# Johnny_5.net
KiCad netlist of a schematic drawn in EAGLE
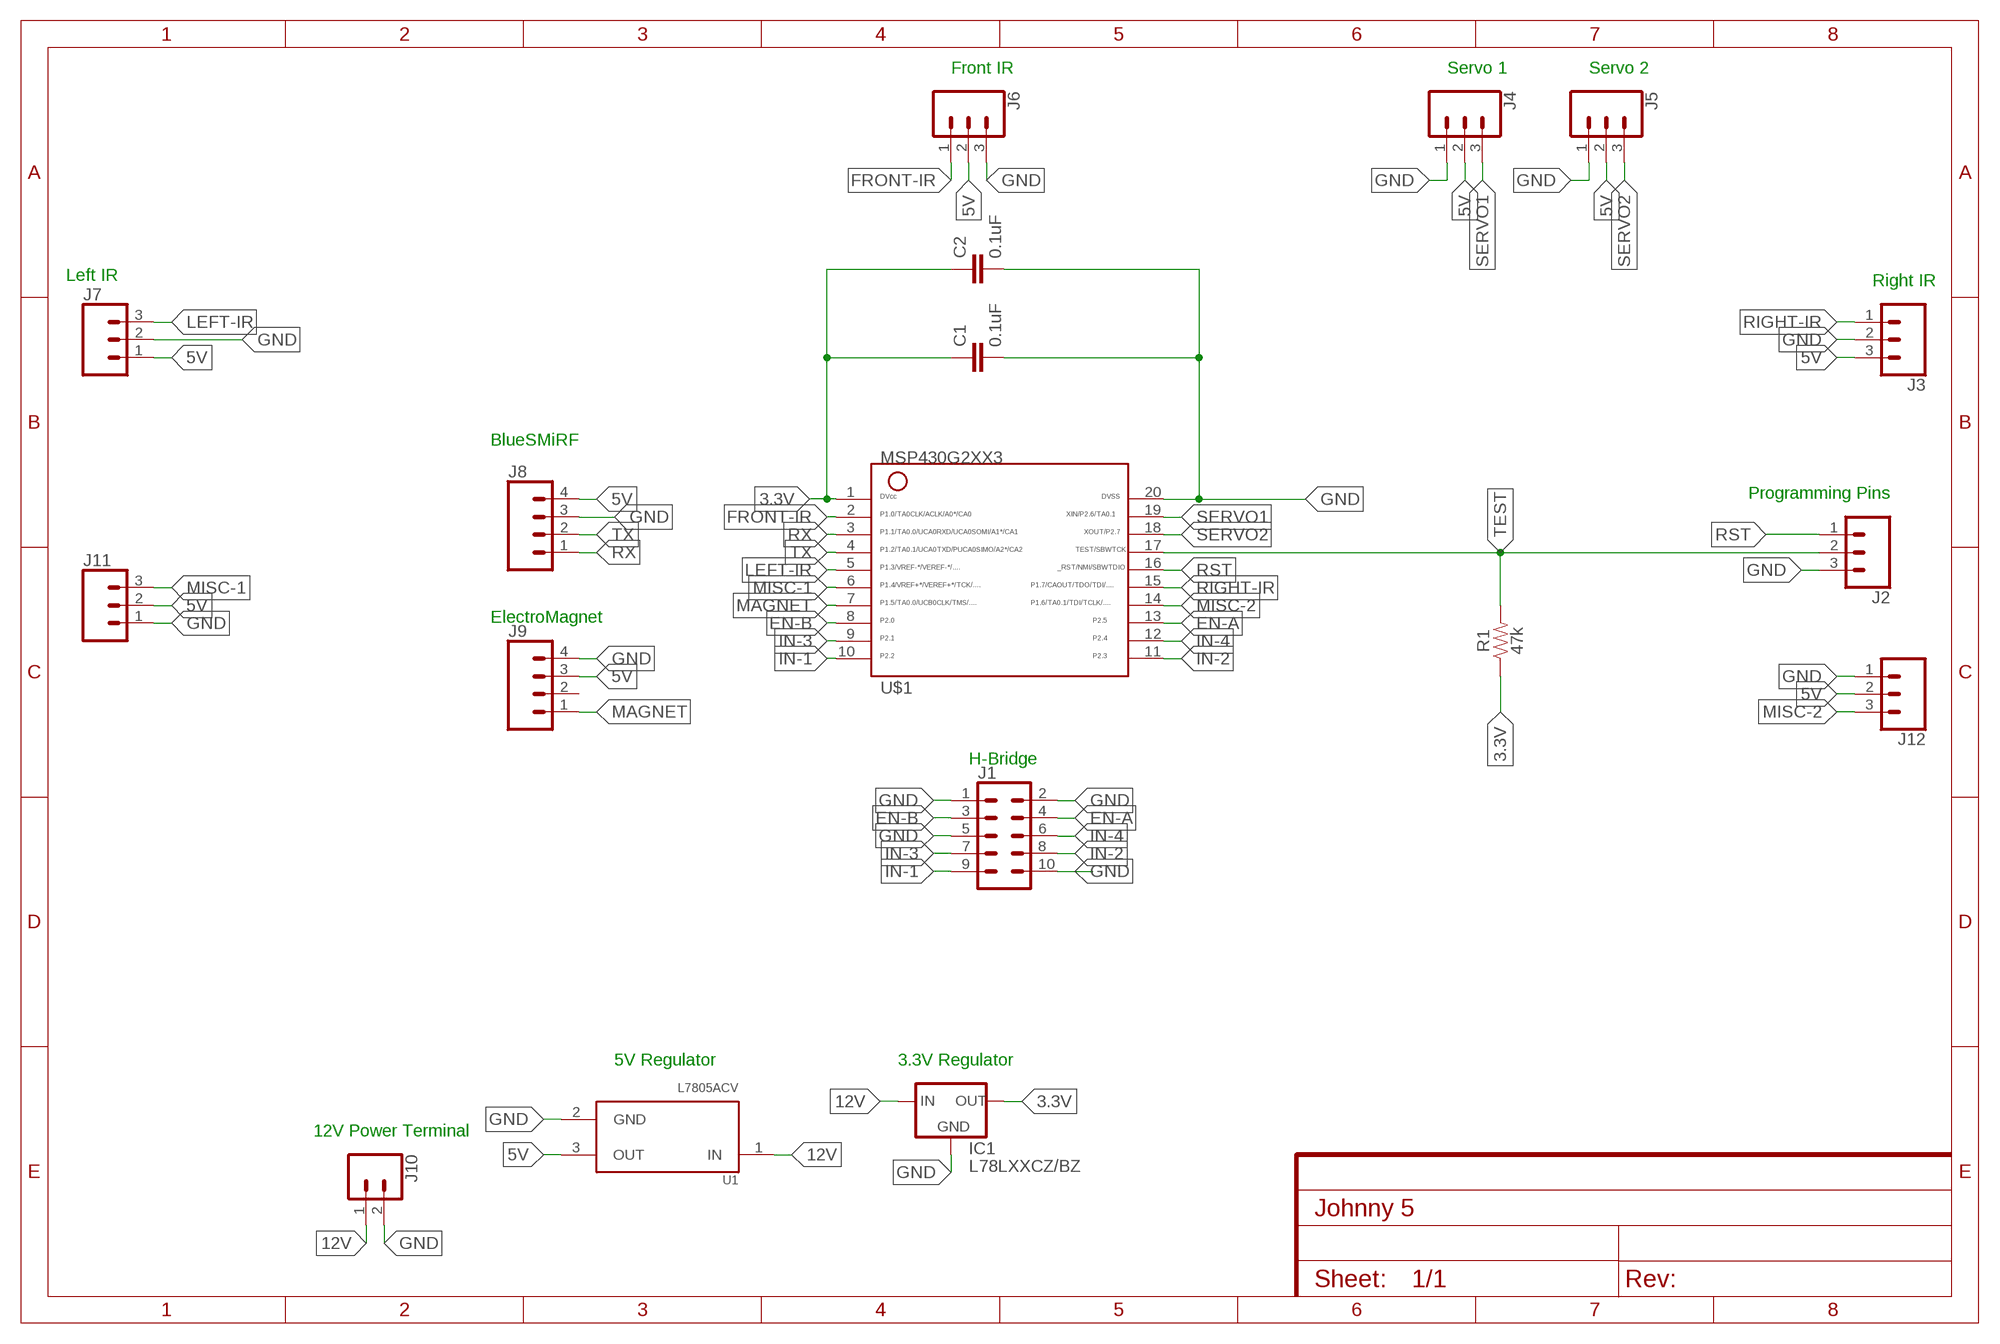
[diagram p0: schematic, sheet 1]

(export (version "E")
  (design (tool "Eeschema 10.0.6"))
  (components
    (comp (ref "C1")
      (value "0.1uF")
      (footprint "eagle-import:CAP-PTH-SMALL-KIT")
      (libsource (lib "eagle-import") (part "0.1UF-KIT-EZ-50V-20%"))
    )
    (comp (ref "C2")
      (value "0.1uF")
      (footprint "eagle-import:CAP-PTH-SMALL-KIT")
      (libsource (lib "eagle-import") (part "0.1UF-KIT-EZ-50V-20%"))
    )
    (comp (ref "IC1")
      (value "L78LXXCZ/BZ")
      (footprint "eagle-import:TO92")
      (libsource (lib "eagle-import") (part "L78LXXCZ/BZ"))
    )
    (comp (ref "J1")
      (value "CONN_05X2SHD")
      (footprint "eagle-import:2X5-SHROUDED")
      (libsource (lib "eagle-import") (part "CONN_05X2SHD"))
    )
    (comp (ref "J2")
      (value "CONN_03")
      (footprint "eagle-import:1X03")
      (libsource (lib "eagle-import") (part "CONN_03"))
    )
    (comp (ref "J3")
      (value "CONN_03")
      (footprint "eagle-import:1X03")
      (libsource (lib "eagle-import") (part "CONN_03"))
    )
    (comp (ref "J4")
      (value "CONN_03")
      (footprint "eagle-import:1X03")
      (libsource (lib "eagle-import") (part "CONN_03"))
    )
    (comp (ref "J5")
      (value "CONN_03")
      (footprint "eagle-import:1X03")
      (libsource (lib "eagle-import") (part "CONN_03"))
    )
    (comp (ref "J6")
      (value "CONN_03")
      (footprint "eagle-import:1X03")
      (libsource (lib "eagle-import") (part "CONN_03"))
    )
    (comp (ref "J7")
      (value "CONN_03")
      (footprint "eagle-import:1X03")
      (libsource (lib "eagle-import") (part "CONN_03"))
    )
    (comp (ref "J8")
      (value "CONN_04")
      (footprint "eagle-import:1X04")
      (libsource (lib "eagle-import") (part "CONN_04"))
    )
    (comp (ref "J9")
      (value "CONN_04")
      (footprint "eagle-import:1X04")
      (libsource (lib "eagle-import") (part "CONN_04"))
    )
    (comp (ref "J10")
      (value "CONN_025MM")
      (footprint "eagle-import:SCREWTERMINAL-5MM-2")
      (libsource (lib "eagle-import") (part "CONN_025MM"))
    )
    (comp (ref "J11")
      (value "CONN_03")
      (footprint "eagle-import:1X03")
      (libsource (lib "eagle-import") (part "CONN_03"))
    )
    (comp (ref "J12")
      (value "CONN_03")
      (footprint "eagle-import:1X03")
      (libsource (lib "eagle-import") (part "CONN_03"))
    )
    (comp (ref "R1")
      (value "47k")
      (footprint "eagle-import:0603")
      (libsource (lib "eagle-import") (part "47KOHM-0603-1/10W-1%"))
    )
    (comp (ref "U$1")
      (value "G2XX3---N20")
      (footprint "eagle-import:N20")
      (libsource (lib "eagle-import") (part "G2XX3---N20"))
    )
    (comp (ref "U1")
      (value "L7805ACV")
      (footprint "eagle-import:TO254P460X1020X1945-3P")
      (fields (field (name "DIGI-KEY_PART_NUMBER") "497-1441-5-ND") (field (name "MF") "STMicroelectronics"))
      (libsource (lib "eagle-import") (part "L7805ACV"))
    )
  )
  (nets
    (net (code "1") (name "3.3V") (class "Default")
      (node (ref "C1") (pin "1") (pinfunction "1_1") (pintype "passive"))
      (node (ref "C2") (pin "1") (pinfunction "1_1") (pintype "passive"))
      (node (ref "IC1") (pin "1") (pinfunction "OUT_1") (pintype "passive"))
      (node (ref "R1") (pin "1") (pinfunction "1_1") (pintype "passive"))
      (node (ref "U$1") (pin "1") (pinfunction "1_1") (pintype "bidirectional"))
    )
    (net (code "2") (name "5V") (class "Default")
      (node (ref "J11") (pin "2") (pinfunction "2_2") (pintype "passive"))
      (node (ref "J12") (pin "2") (pinfunction "2_2") (pintype "passive"))
      (node (ref "J3") (pin "3") (pinfunction "3_3") (pintype "passive"))
      (node (ref "J4") (pin "2") (pinfunction "2_2") (pintype "passive"))
      (node (ref "J5") (pin "2") (pinfunction "2_2") (pintype "passive"))
      (node (ref "J6") (pin "2") (pinfunction "2_2") (pintype "passive"))
      (node (ref "J7") (pin "1") (pinfunction "1_1") (pintype "passive"))
      (node (ref "J8") (pin "4") (pinfunction "4_4") (pintype "passive"))
      (node (ref "J9") (pin "3") (pinfunction "3_3") (pintype "passive"))
      (node (ref "U1") (pin "3") (pinfunction "OUT_3") (pintype "output"))
    )
    (net (code "3") (name "12V") (class "Default")
      (node (ref "IC1") (pin "3") (pinfunction "IN_3") (pintype "input"))
      (node (ref "J10") (pin "1") (pinfunction "1_1") (pintype "passive"))
      (node (ref "U1") (pin "1") (pinfunction "IN_1") (pintype "input"))
    )
    (net (code "4") (name "EN-A") (class "Default")
      (node (ref "J1") (pin "4") (pinfunction "4_4") (pintype "passive"))
      (node (ref "U$1") (pin "13") (pinfunction "13_13") (pintype "bidirectional"))
    )
    (net (code "5") (name "EN-B") (class "Default")
      (node (ref "J1") (pin "3") (pinfunction "3_3") (pintype "passive"))
      (node (ref "U$1") (pin "8") (pinfunction "8_8") (pintype "bidirectional"))
    )
    (net (code "6") (name "FRONT-IR") (class "Default")
      (node (ref "J6") (pin "1") (pinfunction "1_1") (pintype "passive"))
      (node (ref "U$1") (pin "2") (pinfunction "2_2") (pintype "bidirectional"))
    )
    (net (code "7") (name "GND") (class "Default")
      (node (ref "C1") (pin "2") (pinfunction "2_2") (pintype "passive"))
      (node (ref "C2") (pin "2") (pinfunction "2_2") (pintype "passive"))
      (node (ref "IC1") (pin "2") (pinfunction "GND_2") (pintype "input"))
      (node (ref "J1") (pin "1") (pinfunction "1_1") (pintype "passive"))
      (node (ref "J1") (pin "10") (pinfunction "10_10") (pintype "passive"))
      (node (ref "J1") (pin "2") (pinfunction "2_2") (pintype "passive"))
      (node (ref "J1") (pin "5") (pinfunction "5_5") (pintype "passive"))
      (node (ref "J10") (pin "2") (pinfunction "2_2") (pintype "passive"))
      (node (ref "J11") (pin "1") (pinfunction "1_1") (pintype "passive"))
      (node (ref "J12") (pin "1") (pinfunction "1_1") (pintype "passive"))
      (node (ref "J2") (pin "3") (pinfunction "3_3") (pintype "passive"))
      (node (ref "J3") (pin "2") (pinfunction "2_2") (pintype "passive"))
      (node (ref "J4") (pin "1") (pinfunction "1_1") (pintype "passive"))
      (node (ref "J5") (pin "1") (pinfunction "1_1") (pintype "passive"))
      (node (ref "J6") (pin "3") (pinfunction "3_3") (pintype "passive"))
      (node (ref "J7") (pin "2") (pinfunction "2_2") (pintype "passive"))
      (node (ref "J8") (pin "3") (pinfunction "3_3") (pintype "passive"))
      (node (ref "J9") (pin "4") (pinfunction "4_4") (pintype "passive"))
      (node (ref "U$1") (pin "20") (pinfunction "20_20") (pintype "bidirectional"))
      (node (ref "U1") (pin "2") (pinfunction "GND_2") (pintype "power_in"))
    )
    (net (code "8") (name "IN-1") (class "Default")
      (node (ref "J1") (pin "9") (pinfunction "9_9") (pintype "passive"))
      (node (ref "U$1") (pin "10") (pinfunction "10_10") (pintype "bidirectional"))
    )
    (net (code "9") (name "IN-2") (class "Default")
      (node (ref "J1") (pin "8") (pinfunction "8_8") (pintype "passive"))
      (node (ref "U$1") (pin "11") (pinfunction "11_11") (pintype "bidirectional"))
    )
    (net (code "10") (name "IN-3") (class "Default")
      (node (ref "J1") (pin "7") (pinfunction "7_7") (pintype "passive"))
      (node (ref "U$1") (pin "9") (pinfunction "9_9") (pintype "bidirectional"))
    )
    (net (code "11") (name "IN-4") (class "Default")
      (node (ref "J1") (pin "6") (pinfunction "6_6") (pintype "passive"))
      (node (ref "U$1") (pin "12") (pinfunction "12_12") (pintype "bidirectional"))
    )
    (net (code "12") (name "LEFT-IR") (class "Default")
      (node (ref "J7") (pin "3") (pinfunction "3_3") (pintype "passive"))
      (node (ref "U$1") (pin "5") (pinfunction "5_5") (pintype "bidirectional"))
    )
    (net (code "13") (name "MAGNET") (class "Default")
      (node (ref "J9") (pin "1") (pinfunction "1_1") (pintype "passive"))
      (node (ref "U$1") (pin "7") (pinfunction "7_7") (pintype "bidirectional"))
    )
    (net (code "14") (name "MISC-1") (class "Default")
      (node (ref "J11") (pin "3") (pinfunction "3_3") (pintype "passive"))
      (node (ref "U$1") (pin "6") (pinfunction "6_6") (pintype "bidirectional"))
    )
    (net (code "15") (name "MISC-2") (class "Default")
      (node (ref "J12") (pin "3") (pinfunction "3_3") (pintype "passive"))
      (node (ref "U$1") (pin "14") (pinfunction "14_14") (pintype "bidirectional"))
    )
    (net (code "16") (name "RIGHT-IR") (class "Default")
      (node (ref "J3") (pin "1") (pinfunction "1_1") (pintype "passive"))
      (node (ref "U$1") (pin "15") (pinfunction "15_15") (pintype "bidirectional"))
    )
    (net (code "17") (name "RST") (class "Default")
      (node (ref "J2") (pin "1") (pinfunction "1_1") (pintype "passive"))
      (node (ref "U$1") (pin "16") (pinfunction "16_16") (pintype "bidirectional"))
    )
    (net (code "18") (name "RX") (class "Default")
      (node (ref "J8") (pin "1") (pinfunction "1_1") (pintype "passive"))
      (node (ref "U$1") (pin "3") (pinfunction "3_3") (pintype "bidirectional"))
    )
    (net (code "19") (name "SERVO1") (class "Default")
      (node (ref "J4") (pin "3") (pinfunction "3_3") (pintype "passive"))
      (node (ref "U$1") (pin "19") (pinfunction "19_19") (pintype "bidirectional"))
    )
    (net (code "20") (name "SERVO2") (class "Default")
      (node (ref "J5") (pin "3") (pinfunction "3_3") (pintype "passive"))
      (node (ref "U$1") (pin "18") (pinfunction "18_18") (pintype "bidirectional"))
    )
    (net (code "21") (name "TEST") (class "Default")
      (node (ref "J2") (pin "2") (pinfunction "2_2") (pintype "passive"))
      (node (ref "R1") (pin "2") (pinfunction "2_2") (pintype "passive"))
      (node (ref "U$1") (pin "17") (pinfunction "17_17") (pintype "bidirectional"))
    )
    (net (code "22") (name "TX") (class "Default")
      (node (ref "J8") (pin "2") (pinfunction "2_2") (pintype "passive"))
      (node (ref "U$1") (pin "4") (pinfunction "4_4") (pintype "bidirectional"))
    )
    (net (code "23") (name "unconnected-(J9-Pad2)") (class "Default")
      (node (ref "J9") (pin "2") (pinfunction "2_2") (pintype "passive"))
    )
  )
)
